# MCU.net
KiCad netlist of a schematic drawn in Altium Designer
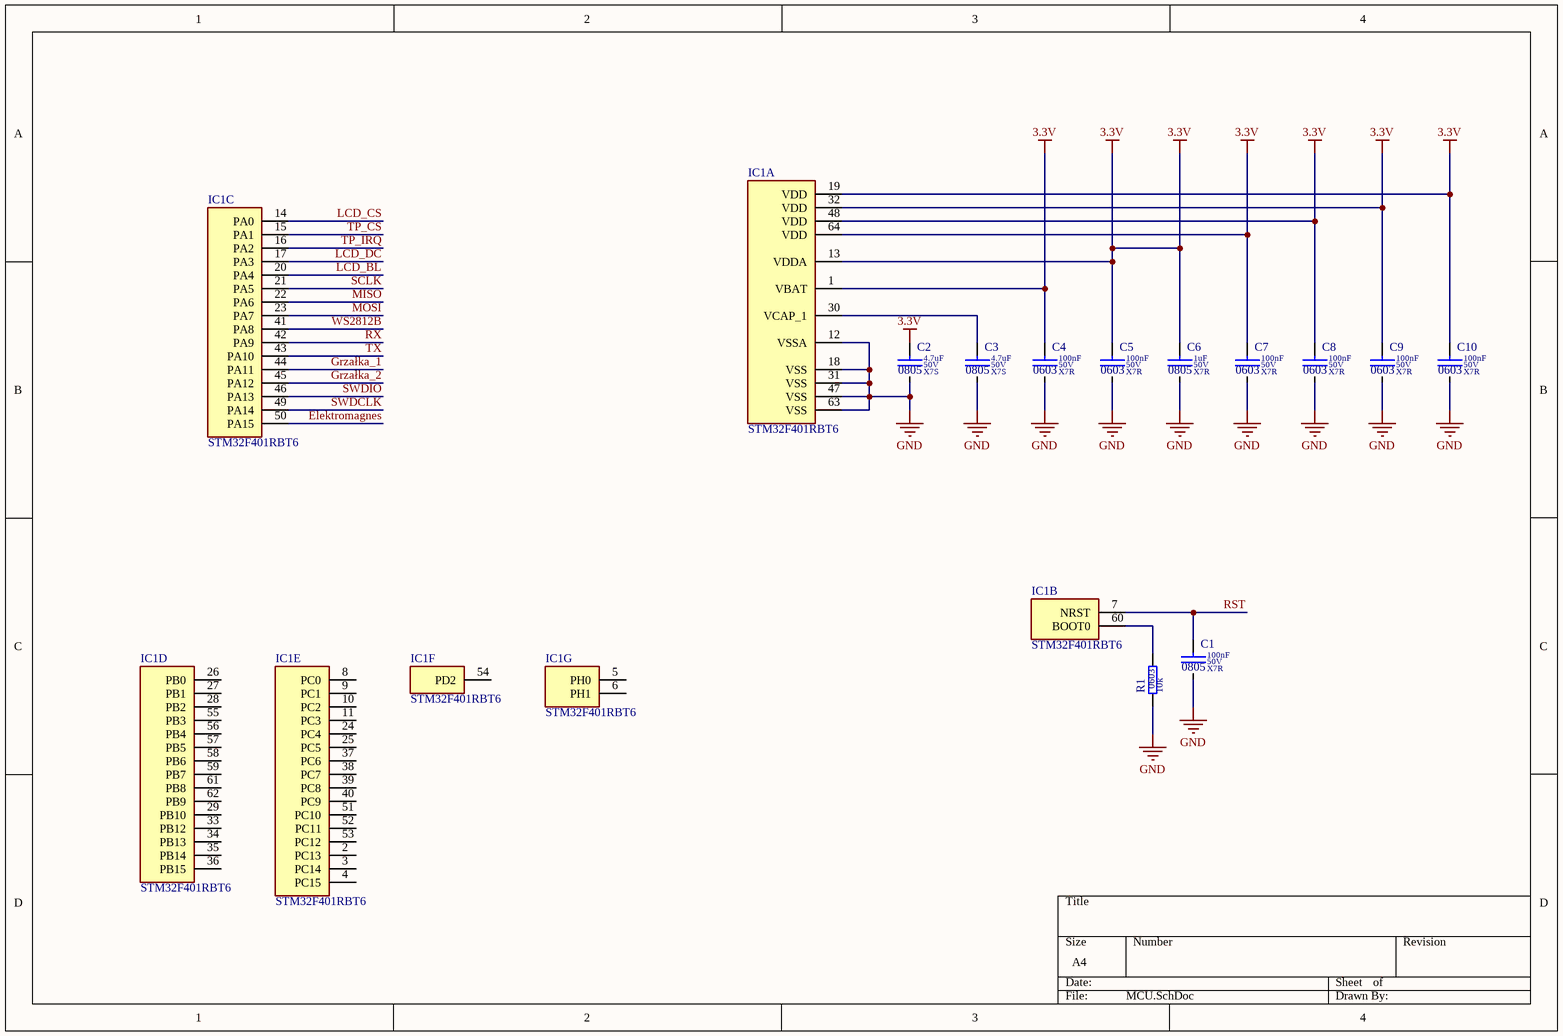
[diagram p0: MCU.SchDoc]

(export (version "E")
  (design (tool "Eeschema 10.0.6"))
  (components
    (comp (ref "C1")
      (value "100nF")
      (footprint "C_0805_2012")
      (description "Capacitor")
      (fields
        (field (name "DIELECTRIC") "X7R")
        (field (name "VOLTAGE") "50V")
        (field (name "SCH_FOOTPRINT") "0805")
        (field (name "PART NUMBER") "C_100nF_50V_X7R_0805_10")
        (field (name "MANUFACTURER") "AVX")
      )
      (libsource (lib "Library") (part "C"))
    )
    (comp (ref "C2")
      (value "4.7uF")
      (footprint "C_0805_2012")
      (description "Capacitor")
      (fields
        (field (name "DIELECTRIC") "X7S")
        (field (name "VOLTAGE") "50V")
        (field (name "SCH_FOOTPRINT") "0805")
        (field (name "PART NUMBER") "C_4.7uF_50V_X7S_0805_10")
        (field (name "MANUFACTURER") "Murata")
      )
      (libsource (lib "Library") (part "C"))
    )
    (comp (ref "C3")
      (value "4.7uF")
      (footprint "C_0805_2012")
      (description "Capacitor")
      (fields
        (field (name "DIELECTRIC") "X7S")
        (field (name "VOLTAGE") "50V")
        (field (name "SCH_FOOTPRINT") "0805")
        (field (name "PART NUMBER") "C_4.7uF_50V_X7S_0805_10")
        (field (name "MANUFACTURER") "Murata")
      )
      (libsource (lib "Library") (part "C"))
    )
    (comp (ref "C4")
      (value "100nF")
      (footprint "C_0603_1608")
      (description "Capacitor")
      (fields
        (field (name "DIELECTRIC") "X7R")
        (field (name "VOLTAGE") "50V")
        (field (name "SCH_FOOTPRINT") "0603")
        (field (name "PART NUMBER") "C_100nF_50V_X7R_0603_5")
        (field (name "MANUFACTURER") "Samsung")
      )
      (libsource (lib "Library") (part "C"))
    )
    (comp (ref "C5")
      (value "100nF")
      (footprint "C_0603_1608")
      (description "Capacitor")
      (fields
        (field (name "DIELECTRIC") "X7R")
        (field (name "VOLTAGE") "50V")
        (field (name "SCH_FOOTPRINT") "0603")
        (field (name "PART NUMBER") "C_100nF_50V_X7R_0603_5")
        (field (name "MANUFACTURER") "Samsung")
      )
      (libsource (lib "Library") (part "C"))
    )
    (comp (ref "C6")
      (value "1uF")
      (footprint "C_0805_2012")
      (description "Capacitor")
      (fields
        (field (name "DIELECTRIC") "X7R")
        (field (name "VOLTAGE") "50V")
        (field (name "SCH_FOOTPRINT") "0805")
        (field (name "PART NUMBER") "C_1uF_50V_X7R_0805_10")
        (field (name "MANUFACTURER") "AVX")
      )
      (libsource (lib "Library") (part "C"))
    )
    (comp (ref "C7")
      (value "100nF")
      (footprint "C_0603_1608")
      (description "Capacitor")
      (fields
        (field (name "DIELECTRIC") "X7R")
        (field (name "VOLTAGE") "50V")
        (field (name "SCH_FOOTPRINT") "0603")
        (field (name "PART NUMBER") "C_100nF_50V_X7R_0603_5")
        (field (name "MANUFACTURER") "Samsung")
      )
      (libsource (lib "Library") (part "C"))
    )
    (comp (ref "C8")
      (value "100nF")
      (footprint "C_0603_1608")
      (description "Capacitor")
      (fields
        (field (name "DIELECTRIC") "X7R")
        (field (name "VOLTAGE") "50V")
        (field (name "SCH_FOOTPRINT") "0603")
        (field (name "PART NUMBER") "C_100nF_50V_X7R_0603_5")
        (field (name "MANUFACTURER") "Samsung")
      )
      (libsource (lib "Library") (part "C"))
    )
    (comp (ref "C9")
      (value "100nF")
      (footprint "C_0603_1608")
      (description "Capacitor")
      (fields
        (field (name "DIELECTRIC") "X7R")
        (field (name "VOLTAGE") "50V")
        (field (name "SCH_FOOTPRINT") "0603")
        (field (name "PART NUMBER") "C_100nF_50V_X7R_0603_5")
        (field (name "MANUFACTURER") "Samsung")
      )
      (libsource (lib "Library") (part "C"))
    )
    (comp (ref "C10")
      (value "100nF")
      (footprint "C_0603_1608")
      (description "Capacitor")
      (fields
        (field (name "DIELECTRIC") "X7R")
        (field (name "VOLTAGE") "50V")
        (field (name "SCH_FOOTPRINT") "0603")
        (field (name "PART NUMBER") "C_100nF_50V_X7R_0603_5")
        (field (name "MANUFACTURER") "Samsung")
      )
      (libsource (lib "Library") (part "C"))
    )
    (comp (ref "IC1")
      (value "STM32F401RBT6")
      (footprint "LQFP-64")
      (description "ARM Microcontroller")
      (libsource (lib "Components") (part "STM32F401RBT6"))
    )
    (comp (ref "R1")
      (value "10k")
      (footprint "R_0603_1608")
      (fields
        (field (name "SCH_FOOTPRINT") "0603")
        (field (name "PART NUMBER") "R_10k_0603_1")
        (field (name "VOLTAGE") "75V")
        (field (name "POWER") "100mW")
      )
      (libsource (lib "Library") (part "R"))
    )
  )
  (nets
    (net (code "1") (name "/Elektromagnes") (class "Default")
      (node (ref "IC1") (pin "50") (pinfunction "PA15_50") (pintype "passive"))
    )
    (net (code "2") (name "/Grzałka_1") (class "Default")
      (node (ref "IC1") (pin "44") (pinfunction "PA11_44") (pintype "passive"))
    )
    (net (code "3") (name "/Grzałka_2") (class "Default")
      (node (ref "IC1") (pin "45") (pinfunction "PA12_45") (pintype "passive"))
    )
    (net (code "4") (name "/LCD_BL") (class "Default")
      (node (ref "IC1") (pin "20") (pinfunction "PA4_20") (pintype "passive"))
    )
    (net (code "5") (name "/LCD_CS") (class "Default")
      (node (ref "IC1") (pin "14") (pinfunction "PA0_14") (pintype "passive"))
    )
    (net (code "6") (name "/LCD_DC") (class "Default")
      (node (ref "IC1") (pin "17") (pinfunction "PA3_17") (pintype "passive"))
    )
    (net (code "7") (name "/MISO") (class "Default")
      (node (ref "IC1") (pin "22") (pinfunction "PA6_22") (pintype "passive"))
    )
    (net (code "8") (name "/MOSI") (class "Default")
      (node (ref "IC1") (pin "23") (pinfunction "PA7_23") (pintype "passive"))
    )
    (net (code "9") (name "/RST") (class "Default")
      (node (ref "C1") (pin "1") (pinfunction "1_1") (pintype "passive"))
      (node (ref "IC1") (pin "7") (pinfunction "NRST_7") (pintype "passive"))
    )
    (net (code "10") (name "/RX") (class "Default")
      (node (ref "IC1") (pin "42") (pinfunction "PA9_42") (pintype "passive"))
    )
    (net (code "11") (name "/SCLK") (class "Default")
      (node (ref "IC1") (pin "21") (pinfunction "PA5_21") (pintype "passive"))
    )
    (net (code "12") (name "/SWDCLK") (class "Default")
      (node (ref "IC1") (pin "49") (pinfunction "PA14_49") (pintype "passive"))
    )
    (net (code "13") (name "/SWDIO") (class "Default")
      (node (ref "IC1") (pin "46") (pinfunction "PA13_46") (pintype "passive"))
    )
    (net (code "14") (name "/TP_CS") (class "Default")
      (node (ref "IC1") (pin "15") (pinfunction "PA1_15") (pintype "passive"))
    )
    (net (code "15") (name "/TP_IRQ") (class "Default")
      (node (ref "IC1") (pin "16") (pinfunction "PA2_16") (pintype "passive"))
    )
    (net (code "16") (name "/TX") (class "Default")
      (node (ref "IC1") (pin "43") (pinfunction "PA10_43") (pintype "passive"))
    )
    (net (code "17") (name "/WS2812B") (class "Default")
      (node (ref "IC1") (pin "41") (pinfunction "PA8_41") (pintype "passive"))
    )
    (net (code "18") (name "3.3V") (class "Default")
      (node (ref "C10") (pin "1") (pinfunction "1_1") (pintype "passive"))
      (node (ref "C2") (pin "1") (pinfunction "1_1") (pintype "passive"))
      (node (ref "C4") (pin "1") (pinfunction "1_1") (pintype "passive"))
      (node (ref "C5") (pin "1") (pinfunction "1_1") (pintype "passive"))
      (node (ref "C6") (pin "1") (pinfunction "1_1") (pintype "passive"))
      (node (ref "C7") (pin "1") (pinfunction "1_1") (pintype "passive"))
      (node (ref "C8") (pin "1") (pinfunction "1_1") (pintype "passive"))
      (node (ref "C9") (pin "1") (pinfunction "1_1") (pintype "passive"))
      (node (ref "IC1") (pin "1") (pinfunction "VBAT_1") (pintype "passive"))
      (node (ref "IC1") (pin "13") (pinfunction "VDDA_13") (pintype "passive"))
      (node (ref "IC1") (pin "19") (pinfunction "VDD_19") (pintype "passive"))
      (node (ref "IC1") (pin "32") (pinfunction "VDD_32") (pintype "passive"))
      (node (ref "IC1") (pin "48") (pinfunction "VDD_48") (pintype "passive"))
      (node (ref "IC1") (pin "64") (pinfunction "VDD_64") (pintype "passive"))
    )
    (net (code "19") (name "GND") (class "Default")
      (node (ref "C1") (pin "2") (pinfunction "2_2") (pintype "passive"))
      (node (ref "C10") (pin "2") (pinfunction "2_2") (pintype "passive"))
      (node (ref "C2") (pin "2") (pinfunction "2_2") (pintype "passive"))
      (node (ref "C3") (pin "2") (pinfunction "2_2") (pintype "passive"))
      (node (ref "C4") (pin "2") (pinfunction "2_2") (pintype "passive"))
      (node (ref "C5") (pin "2") (pinfunction "2_2") (pintype "passive"))
      (node (ref "C6") (pin "2") (pinfunction "2_2") (pintype "passive"))
      (node (ref "C7") (pin "2") (pinfunction "2_2") (pintype "passive"))
      (node (ref "C8") (pin "2") (pinfunction "2_2") (pintype "passive"))
      (node (ref "C9") (pin "2") (pinfunction "2_2") (pintype "passive"))
      (node (ref "IC1") (pin "12") (pinfunction "VSSA_12") (pintype "passive"))
      (node (ref "IC1") (pin "18") (pinfunction "VSS_18") (pintype "passive"))
      (node (ref "IC1") (pin "31") (pinfunction "VSS_31") (pintype "passive"))
      (node (ref "IC1") (pin "47") (pinfunction "VSS_47") (pintype "passive"))
      (node (ref "IC1") (pin "63") (pinfunction "VSS_63") (pintype "passive"))
      (node (ref "R1") (pin "1") (pinfunction "1_1") (pintype "passive"))
    )
    (net (code "20") (name "Net-(IC1A-VCAP_1)") (class "Default")
      (node (ref "C3") (pin "1") (pinfunction "1_1") (pintype "passive"))
      (node (ref "IC1") (pin "30") (pinfunction "VCAP_1_30") (pintype "passive"))
    )
    (net (code "21") (name "Net-(IC1B-BOOT0)") (class "Default")
      (node (ref "IC1") (pin "60") (pinfunction "BOOT0_60") (pintype "passive"))
      (node (ref "R1") (pin "2") (pinfunction "2_2") (pintype "passive"))
    )
    (net (code "22") (name "unconnected-(IC1D-PB0-Pad26)") (class "Default")
      (node (ref "IC1") (pin "26") (pinfunction "PB0_26") (pintype "passive"))
    )
    (net (code "23") (name "unconnected-(IC1D-PB1-Pad27)") (class "Default")
      (node (ref "IC1") (pin "27") (pinfunction "PB1_27") (pintype "passive"))
    )
    (net (code "24") (name "unconnected-(IC1D-PB2-Pad28)") (class "Default")
      (node (ref "IC1") (pin "28") (pinfunction "PB2_28") (pintype "passive"))
    )
    (net (code "25") (name "unconnected-(IC1D-PB3-Pad55)") (class "Default")
      (node (ref "IC1") (pin "55") (pinfunction "PB3_55") (pintype "passive"))
    )
    (net (code "26") (name "unconnected-(IC1D-PB4-Pad56)") (class "Default")
      (node (ref "IC1") (pin "56") (pinfunction "PB4_56") (pintype "passive"))
    )
    (net (code "27") (name "unconnected-(IC1D-PB5-Pad57)") (class "Default")
      (node (ref "IC1") (pin "57") (pinfunction "PB5_57") (pintype "passive"))
    )
    (net (code "28") (name "unconnected-(IC1D-PB6-Pad58)") (class "Default")
      (node (ref "IC1") (pin "58") (pinfunction "PB6_58") (pintype "passive"))
    )
    (net (code "29") (name "unconnected-(IC1D-PB7-Pad59)") (class "Default")
      (node (ref "IC1") (pin "59") (pinfunction "PB7_59") (pintype "passive"))
    )
    (net (code "30") (name "unconnected-(IC1D-PB8-Pad61)") (class "Default")
      (node (ref "IC1") (pin "61") (pinfunction "PB8_61") (pintype "passive"))
    )
    (net (code "31") (name "unconnected-(IC1D-PB9-Pad62)") (class "Default")
      (node (ref "IC1") (pin "62") (pinfunction "PB9_62") (pintype "passive"))
    )
    (net (code "32") (name "unconnected-(IC1D-PB10-Pad29)") (class "Default")
      (node (ref "IC1") (pin "29") (pinfunction "PB10_29") (pintype "passive"))
    )
    (net (code "33") (name "unconnected-(IC1D-PB12-Pad33)") (class "Default")
      (node (ref "IC1") (pin "33") (pinfunction "PB12_33") (pintype "passive"))
    )
    (net (code "34") (name "unconnected-(IC1D-PB13-Pad34)") (class "Default")
      (node (ref "IC1") (pin "34") (pinfunction "PB13_34") (pintype "passive"))
    )
    (net (code "35") (name "unconnected-(IC1D-PB14-Pad35)") (class "Default")
      (node (ref "IC1") (pin "35") (pinfunction "PB14_35") (pintype "passive"))
    )
    (net (code "36") (name "unconnected-(IC1D-PB15-Pad36)") (class "Default")
      (node (ref "IC1") (pin "36") (pinfunction "PB15_36") (pintype "passive"))
    )
    (net (code "37") (name "unconnected-(IC1E-PC0-Pad8)") (class "Default")
      (node (ref "IC1") (pin "8") (pinfunction "PC0_8") (pintype "passive"))
    )
    (net (code "38") (name "unconnected-(IC1E-PC1-Pad9)") (class "Default")
      (node (ref "IC1") (pin "9") (pinfunction "PC1_9") (pintype "passive"))
    )
    (net (code "39") (name "unconnected-(IC1E-PC2-Pad10)") (class "Default")
      (node (ref "IC1") (pin "10") (pinfunction "PC2_10") (pintype "passive"))
    )
    (net (code "40") (name "unconnected-(IC1E-PC3-Pad11)") (class "Default")
      (node (ref "IC1") (pin "11") (pinfunction "PC3_11") (pintype "passive"))
    )
    (net (code "41") (name "unconnected-(IC1E-PC4-Pad24)") (class "Default")
      (node (ref "IC1") (pin "24") (pinfunction "PC4_24") (pintype "passive"))
    )
    (net (code "42") (name "unconnected-(IC1E-PC5-Pad25)") (class "Default")
      (node (ref "IC1") (pin "25") (pinfunction "PC5_25") (pintype "passive"))
    )
    (net (code "43") (name "unconnected-(IC1E-PC6-Pad37)") (class "Default")
      (node (ref "IC1") (pin "37") (pinfunction "PC6_37") (pintype "passive"))
    )
    (net (code "44") (name "unconnected-(IC1E-PC7-Pad38)") (class "Default")
      (node (ref "IC1") (pin "38") (pinfunction "PC7_38") (pintype "passive"))
    )
    (net (code "45") (name "unconnected-(IC1E-PC8-Pad39)") (class "Default")
      (node (ref "IC1") (pin "39") (pinfunction "PC8_39") (pintype "passive"))
    )
    (net (code "46") (name "unconnected-(IC1E-PC9-Pad40)") (class "Default")
      (node (ref "IC1") (pin "40") (pinfunction "PC9_40") (pintype "passive"))
    )
    (net (code "47") (name "unconnected-(IC1E-PC10-Pad51)") (class "Default")
      (node (ref "IC1") (pin "51") (pinfunction "PC10_51") (pintype "passive"))
    )
    (net (code "48") (name "unconnected-(IC1E-PC11-Pad52)") (class "Default")
      (node (ref "IC1") (pin "52") (pinfunction "PC11_52") (pintype "passive"))
    )
    (net (code "49") (name "unconnected-(IC1E-PC12-Pad53)") (class "Default")
      (node (ref "IC1") (pin "53") (pinfunction "PC12_53") (pintype "passive"))
    )
    (net (code "50") (name "unconnected-(IC1E-PC13-Pad2)") (class "Default")
      (node (ref "IC1") (pin "2") (pinfunction "PC13_2") (pintype "passive"))
    )
    (net (code "51") (name "unconnected-(IC1E-PC14-Pad3)") (class "Default")
      (node (ref "IC1") (pin "3") (pinfunction "PC14_3") (pintype "passive"))
    )
    (net (code "52") (name "unconnected-(IC1E-PC15-Pad4)") (class "Default")
      (node (ref "IC1") (pin "4") (pinfunction "PC15_4") (pintype "passive"))
    )
    (net (code "53") (name "unconnected-(IC1F-PD2-Pad54)") (class "Default")
      (node (ref "IC1") (pin "54") (pinfunction "PD2_54") (pintype "passive"))
    )
    (net (code "54") (name "unconnected-(IC1G-PH0-Pad5)") (class "Default")
      (node (ref "IC1") (pin "5") (pinfunction "PH0_5") (pintype "passive"))
    )
    (net (code "55") (name "unconnected-(IC1G-PH1-Pad6)") (class "Default")
      (node (ref "IC1") (pin "6") (pinfunction "PH1_6") (pintype "passive"))
    )
  )
)
